# SHO-V1_1.net
KiCad netlist of a schematic drawn in EAGLE
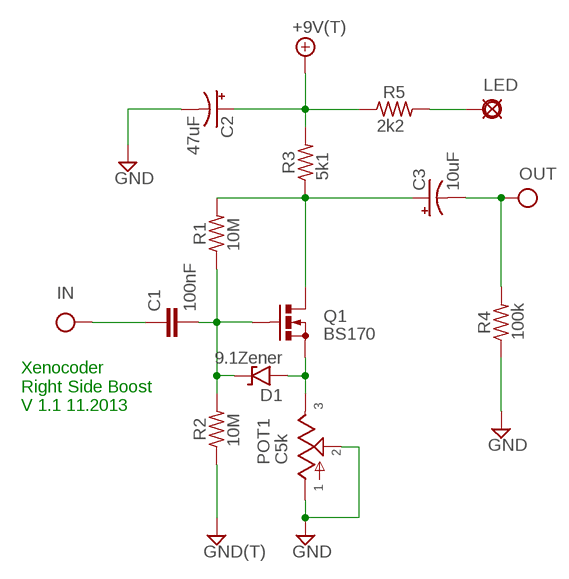
[diagram p0: schematic, sheet 1]

(export (version "E")
  (design (tool "Eeschema 10.0.6"))
  (components
    (comp (ref "+9V")
      (value "+9V(T)")
      (footprint "eagle-import:SQUARE")
      (libsource (lib "eagle-import") (part "+9V(T)"))
    )
    (comp (ref "C1")
      (value "100nF")
      (footprint "eagle-import:075X030")
      (libsource (lib "eagle-import") (part "075X0302"))
    )
    (comp (ref "C2")
      (value "47uF")
      (footprint "eagle-import:063_025")
      (libsource (lib "eagle-import") (part "0631"))
    )
    (comp (ref "C3")
      (value "10uF")
      (footprint "eagle-import:063_025")
      (libsource (lib "eagle-import") (part "0631"))
    )
    (comp (ref "D1")
      (value "9.1Zener")
      (footprint "eagle-import:DO35-3")
      (libsource (lib "eagle-import") (part "1N9ZENER"))
    )
    (comp (ref "GND")
      (value "GND(T)")
      (footprint "eagle-import:SQUARE")
      (libsource (lib "eagle-import") (part "GND(T)"))
    )
    (comp (ref "IN")
      (value "IN(T)")
      (footprint "eagle-import:SQUARE")
      (libsource (lib "eagle-import") (part "IN(T)"))
    )
    (comp (ref "LED")
      (value "3mm")
      (footprint "eagle-import:SQUARE")
      (libsource (lib "eagle-import") (part "PAD"))
    )
    (comp (ref "OUT")
      (value "OUT(T)")
      (footprint "eagle-import:SQUARE")
      (libsource (lib "eagle-import") (part "OUT(T)"))
    )
    (comp (ref "POT1")
      (value "C5k")
      (footprint "eagle-import:16MM_PCB_PADS")
      (libsource (lib "eagle-import") (part "POT16MM_PCB_PADS"))
    )
    (comp (ref "Q1")
      (value "BS170")
      (footprint "eagle-import:SOT54ES")
      (libsource (lib "eagle-import") (part "BS170"))
    )
    (comp (ref "R1")
      (value "10M")
      (footprint "eagle-import:R0207_3")
      (libsource (lib "eagle-import") (part "6MM.3"))
    )
    (comp (ref "R2")
      (value "10M")
      (footprint "eagle-import:R0207_3")
      (libsource (lib "eagle-import") (part "6MM.3"))
    )
    (comp (ref "R3")
      (value "5k1")
      (footprint "eagle-import:R0207_3")
      (libsource (lib "eagle-import") (part "6MM.3"))
    )
    (comp (ref "R4")
      (value "100k")
      (footprint "eagle-import:R0207_3")
      (libsource (lib "eagle-import") (part "6MM.3"))
    )
    (comp (ref "R5")
      (value "2k2")
      (footprint "eagle-import:R0207_3")
      (libsource (lib "eagle-import") (part "6MM.3"))
    )
  )
  (nets
    (net (code "1") (name "+9V(T)") (class "Default")
      (node (ref "+9V") (pin "1") (pinfunction "+9V_1") (pintype "power_in"))
      (node (ref "C2") (pin "+") (pinfunction "+_+") (pintype "passive"))
      (node (ref "R3") (pin "2") (pinfunction "2_2") (pintype "passive"))
      (node (ref "R5") (pin "1") (pinfunction "1_1") (pintype "passive"))
    )
    (net (code "2") (name "GND") (class "Default")
      (node (ref "C2") (pin "-") (pinfunction "-_-") (pintype "passive"))
      (node (ref "GND") (pin "1") (pinfunction "GND_1") (pintype "power_in"))
      (node (ref "POT1") (pin "1") (pinfunction "1_1") (pintype "passive"))
      (node (ref "POT1") (pin "2") (pinfunction "2_2") (pintype "passive"))
      (node (ref "R2") (pin "1") (pinfunction "1_1") (pintype "passive"))
      (node (ref "R4") (pin "1") (pinfunction "1_1") (pintype "passive"))
    )
    (net (code "3") (name "IN(T)") (class "Default")
      (node (ref "C1") (pin "1") (pinfunction "1_1") (pintype "passive"))
      (node (ref "IN") (pin "1") (pinfunction "IN_1") (pintype "power_in"))
    )
    (net (code "4") (name "Net-(C1-Pad2)") (class "Default")
      (node (ref "C1") (pin "2") (pinfunction "2_2") (pintype "passive"))
      (node (ref "D1") (pin "C") (pinfunction "C_C") (pintype "passive"))
      (node (ref "Q1") (pin "G") (pinfunction "G_G") (pintype "passive"))
      (node (ref "R1") (pin "1") (pinfunction "1_1") (pintype "passive"))
      (node (ref "R2") (pin "2") (pinfunction "2_2") (pintype "passive"))
    )
    (net (code "5") (name "Net-(C3-Pad+)") (class "Default")
      (node (ref "C3") (pin "+") (pinfunction "+_+") (pintype "passive"))
      (node (ref "Q1") (pin "D") (pinfunction "D_D") (pintype "passive"))
      (node (ref "R1") (pin "2") (pinfunction "2_2") (pintype "passive"))
      (node (ref "R3") (pin "1") (pinfunction "1_1") (pintype "passive"))
    )
    (net (code "6") (name "Net-(D1-PadA)") (class "Default")
      (node (ref "D1") (pin "A") (pinfunction "A_A") (pintype "passive"))
      (node (ref "POT1") (pin "3") (pinfunction "3_3") (pintype "passive"))
      (node (ref "Q1") (pin "S") (pinfunction "S_S") (pintype "passive"))
    )
    (net (code "7") (name "Net-(LED-PAD)") (class "Default")
      (node (ref "LED") (pin "1") (pinfunction "PAD_1") (pintype "passive"))
      (node (ref "R5") (pin "2") (pinfunction "2_2") (pintype "passive"))
    )
    (net (code "8") (name "OUT(T)") (class "Default")
      (node (ref "C3") (pin "-") (pinfunction "-_-") (pintype "passive"))
      (node (ref "OUT") (pin "1") (pinfunction "OUT_1") (pintype "power_in"))
      (node (ref "R4") (pin "2") (pinfunction "2_2") (pintype "passive"))
    )
  )
)
